# piglow.net
KiCad netlist of a schematic drawn in EAGLE
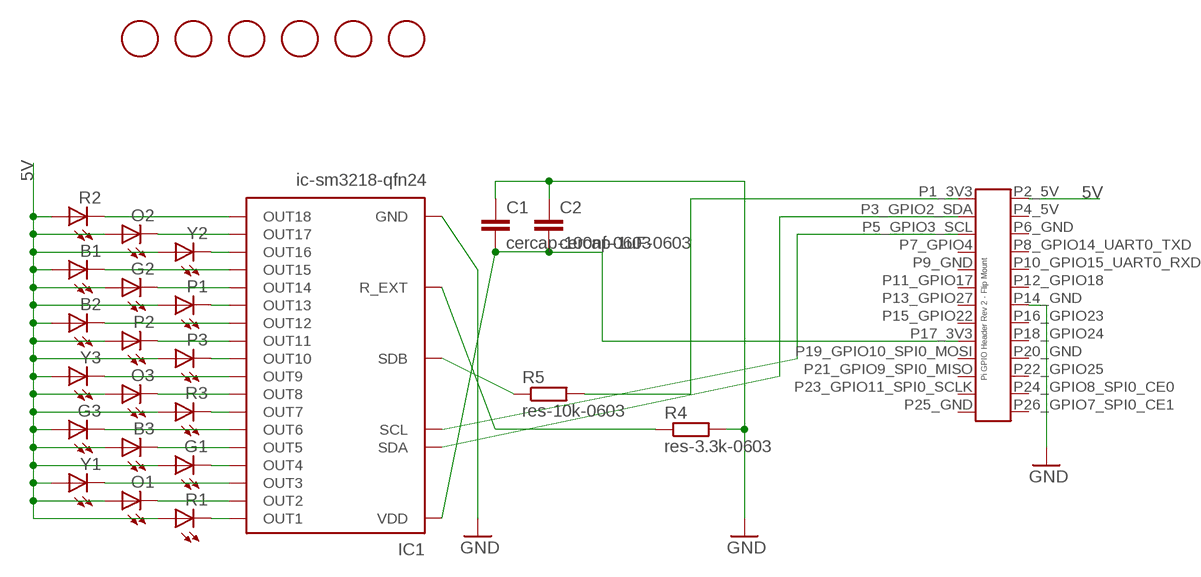
[diagram p0: schematic, sheet 1]

(export (version "E")
  (design (tool "Eeschema 10.0.6"))
  (components
    (comp (ref "B1")
      (value "led-blue-0805")
      (footprint "eagle-import:CHIPLED_0805")
      (libsource (lib "eagle-import") (part "LEDCHIPLED_0805"))
    )
    (comp (ref "B2")
      (value "led-blue-0805")
      (footprint "eagle-import:CHIPLED_0805")
      (libsource (lib "eagle-import") (part "LEDCHIPLED_0805"))
    )
    (comp (ref "B3")
      (value "led-blue-0805")
      (footprint "eagle-import:CHIPLED_0805")
      (libsource (lib "eagle-import") (part "LEDCHIPLED_0805"))
    )
    (comp (ref "C1")
      (value "cercap-100nf-0603")
      (footprint "eagle-import:C0603K")
      (libsource (lib "eagle-import") (part "C-EUC0603K"))
    )
    (comp (ref "C2")
      (value "cercap-1uF-0603")
      (footprint "eagle-import:C0603K")
      (libsource (lib "eagle-import") (part "C-EUC0603K"))
    )
    (comp (ref "G1")
      (value "led-green-0805")
      (footprint "eagle-import:CHIPLED_0805")
      (libsource (lib "eagle-import") (part "LEDCHIPLED_0805"))
    )
    (comp (ref "G2")
      (value "led-green-0805")
      (footprint "eagle-import:CHIPLED_0805")
      (libsource (lib "eagle-import") (part "LEDCHIPLED_0805"))
    )
    (comp (ref "G3")
      (value "led-green-0805")
      (footprint "eagle-import:CHIPLED_0805")
      (libsource (lib "eagle-import") (part "LEDCHIPLED_0805"))
    )
    (comp (ref "IC1")
      (value "ic-sm3218-qfn24")
      (footprint "eagle-import:QFN24")
      (libsource (lib "eagle-import") (part "SN3218"))
    )
    (comp (ref "O1")
      (value "led-orange-0805")
      (footprint "eagle-import:CHIPLED_0805")
      (libsource (lib "eagle-import") (part "LEDCHIPLED_0805"))
    )
    (comp (ref "O2")
      (value "led-orange-0805")
      (footprint "eagle-import:CHIPLED_0805")
      (libsource (lib "eagle-import") (part "LEDCHIPLED_0805"))
    )
    (comp (ref "O3")
      (value "led-orange-0805")
      (footprint "eagle-import:CHIPLED_0805")
      (libsource (lib "eagle-import") (part "LEDCHIPLED_0805"))
    )
    (comp (ref "P1")
      (value "led-pink-0805")
      (footprint "eagle-import:CHIPLED_0805")
      (libsource (lib "eagle-import") (part "LEDCHIPLED_0805"))
    )
    (comp (ref "P2")
      (value "led-pink-0805")
      (footprint "eagle-import:CHIPLED_0805")
      (libsource (lib "eagle-import") (part "LEDCHIPLED_0805"))
    )
    (comp (ref "P3")
      (value "led-pink-0805")
      (footprint "eagle-import:CHIPLED_0805")
      (libsource (lib "eagle-import") (part "LEDCHIPLED_0805"))
    )
    (comp (ref "R1")
      (value "led-red-0805")
      (footprint "eagle-import:CHIPLED_0805")
      (libsource (lib "eagle-import") (part "LEDCHIPLED_0805"))
    )
    (comp (ref "R2")
      (value "led-red-0805")
      (footprint "eagle-import:CHIPLED_0805")
      (libsource (lib "eagle-import") (part "LEDCHIPLED_0805"))
    )
    (comp (ref "R3")
      (value "led-red-0805")
      (footprint "eagle-import:CHIPLED_0805")
      (libsource (lib "eagle-import") (part "LEDCHIPLED_0805"))
    )
    (comp (ref "R4")
      (value "res-3.3k-0603")
      (footprint "eagle-import:R0603")
      (libsource (lib "eagle-import") (part "R-EU_R0603"))
    )
    (comp (ref "R5")
      (value "res-10k-0603")
      (footprint "eagle-import:R0603@1")
      (libsource (lib "eagle-import") (part "resistor_R-EU_R0603"))
    )
    (comp (ref "U$1")
      (value "FIDUCIAL")
      (footprint "eagle-import:FIDUCIAL_1MM")
      (libsource (lib "eagle-import") (part "FIDUCIAL"))
    )
    (comp (ref "U$2")
      (value "FIDUCIAL")
      (footprint "eagle-import:FIDUCIAL_1MM")
      (libsource (lib "eagle-import") (part "FIDUCIAL"))
    )
    (comp (ref "U$3")
      (value "FIDUCIAL")
      (footprint "eagle-import:FIDUCIAL_1MM")
      (libsource (lib "eagle-import") (part "FIDUCIAL"))
    )
    (comp (ref "U$4")
      (value "FCI_89898_313LF_26P_CONNECTOR_SMT_FLIPPED")
      (footprint "eagle-import:FCI_89898_313LF_26P_CONNECTOR_SMT_FLIPPED")
      (libsource (lib "eagle-import") (part "FCI_89898_313LF_26P_CONNECTOR_SMT_FLIPPED"))
    )
    (comp (ref "U$5")
      (value "FIDUCIAL")
      (footprint "eagle-import:FIDUCIAL_1MM")
      (libsource (lib "eagle-import") (part "FIDUCIAL"))
    )
    (comp (ref "U$6")
      (value "FIDUCIAL")
      (footprint "eagle-import:FIDUCIAL_1MM")
      (libsource (lib "eagle-import") (part "FIDUCIAL"))
    )
    (comp (ref "U$7")
      (value "FIDUCIAL")
      (footprint "eagle-import:FIDUCIAL_1MM")
      (libsource (lib "eagle-import") (part "FIDUCIAL"))
    )
    (comp (ref "Y1")
      (value "led-yellow-0805")
      (footprint "eagle-import:CHIPLED_0805")
      (libsource (lib "eagle-import") (part "LEDCHIPLED_0805"))
    )
    (comp (ref "Y2")
      (value "led-yellow-0805")
      (footprint "eagle-import:CHIPLED_0805")
      (libsource (lib "eagle-import") (part "LEDCHIPLED_0805"))
    )
    (comp (ref "Y3")
      (value "led-yellow-0805")
      (footprint "eagle-import:CHIPLED_0805")
      (libsource (lib "eagle-import") (part "LEDCHIPLED_0805"))
    )
  )
  (nets
    (net (code "1") (name "/5V") (class "Default")
      (node (ref "B1") (pin "A") (pinfunction "A_A") (pintype "passive"))
      (node (ref "B2") (pin "A") (pinfunction "A_A") (pintype "passive"))
      (node (ref "B3") (pin "A") (pinfunction "A_A") (pintype "passive"))
      (node (ref "G1") (pin "A") (pinfunction "A_A") (pintype "passive"))
      (node (ref "G2") (pin "A") (pinfunction "A_A") (pintype "passive"))
      (node (ref "G3") (pin "A") (pinfunction "A_A") (pintype "passive"))
      (node (ref "O1") (pin "A") (pinfunction "A_A") (pintype "passive"))
      (node (ref "O2") (pin "A") (pinfunction "A_A") (pintype "passive"))
      (node (ref "O3") (pin "A") (pinfunction "A_A") (pintype "passive"))
      (node (ref "P1") (pin "A") (pinfunction "A_A") (pintype "passive"))
      (node (ref "P2") (pin "A") (pinfunction "A_A") (pintype "passive"))
      (node (ref "P3") (pin "A") (pinfunction "A_A") (pintype "passive"))
      (node (ref "R1") (pin "A") (pinfunction "A_A") (pintype "passive"))
      (node (ref "R2") (pin "A") (pinfunction "A_A") (pintype "passive"))
      (node (ref "R3") (pin "A") (pinfunction "A_A") (pintype "passive"))
      (node (ref "U$4") (pin "P2_5V") (pinfunction "P2_5V_P2_5V") (pintype "power_in"))
      (node (ref "Y1") (pin "A") (pinfunction "A_A") (pintype "passive"))
      (node (ref "Y2") (pin "A") (pinfunction "A_A") (pintype "passive"))
      (node (ref "Y3") (pin "A") (pinfunction "A_A") (pintype "passive"))
    )
    (net (code "2") (name "/P4_5V") (class "Default")
      (node (ref "U$4") (pin "P4_5V") (pinfunction "P4_5V_P4_5V") (pintype "power_in"))
    )
    (net (code "3") (name "GND") (class "Default")
      (node (ref "C1") (pin "1") (pinfunction "1_1") (pintype "passive"))
      (node (ref "C2") (pin "1") (pinfunction "1_1") (pintype "passive"))
      (node (ref "IC1") (pin "4") (pinfunction "GND_4") (pintype "bidirectional"))
      (node (ref "IC1") (pin "GND") (pinfunction "GND_GND") (pintype "bidirectional"))
      (node (ref "R4") (pin "2") (pinfunction "2_2") (pintype "passive"))
      (node (ref "U$4") (pin "P14_GND") (pinfunction "P14_GND_P14_GND") (pintype "passive"))
    )
    (net (code "4") (name "Net-(IC1-OUT1)") (class "Default")
      (node (ref "IC1") (pin "7") (pinfunction "OUT1_7") (pintype "bidirectional"))
      (node (ref "R1") (pin "C") (pinfunction "C_C") (pintype "passive"))
    )
    (net (code "5") (name "Net-(IC1-OUT2)") (class "Default")
      (node (ref "IC1") (pin "8") (pinfunction "OUT2_8") (pintype "bidirectional"))
      (node (ref "O1") (pin "C") (pinfunction "C_C") (pintype "passive"))
    )
    (net (code "6") (name "Net-(IC1-OUT3)") (class "Default")
      (node (ref "IC1") (pin "9") (pinfunction "OUT3_9") (pintype "bidirectional"))
      (node (ref "Y1") (pin "C") (pinfunction "C_C") (pintype "passive"))
    )
    (net (code "7") (name "Net-(IC1-OUT4)") (class "Default")
      (node (ref "G1") (pin "C") (pinfunction "C_C") (pintype "passive"))
      (node (ref "IC1") (pin "10") (pinfunction "OUT4_10") (pintype "bidirectional"))
    )
    (net (code "8") (name "Net-(IC1-OUT5)") (class "Default")
      (node (ref "B3") (pin "C") (pinfunction "C_C") (pintype "passive"))
      (node (ref "IC1") (pin "11") (pinfunction "OUT5_11") (pintype "bidirectional"))
    )
    (net (code "9") (name "Net-(IC1-OUT6)") (class "Default")
      (node (ref "G3") (pin "C") (pinfunction "C_C") (pintype "passive"))
      (node (ref "IC1") (pin "12") (pinfunction "OUT6_12") (pintype "bidirectional"))
    )
    (net (code "10") (name "Net-(IC1-OUT7)") (class "Default")
      (node (ref "IC1") (pin "13") (pinfunction "OUT7_13") (pintype "bidirectional"))
      (node (ref "R3") (pin "C") (pinfunction "C_C") (pintype "passive"))
    )
    (net (code "11") (name "Net-(IC1-OUT8)") (class "Default")
      (node (ref "IC1") (pin "14") (pinfunction "OUT8_14") (pintype "bidirectional"))
      (node (ref "O3") (pin "C") (pinfunction "C_C") (pintype "passive"))
    )
    (net (code "12") (name "Net-(IC1-OUT9)") (class "Default")
      (node (ref "IC1") (pin "15") (pinfunction "OUT9_15") (pintype "bidirectional"))
      (node (ref "Y3") (pin "C") (pinfunction "C_C") (pintype "passive"))
    )
    (net (code "13") (name "Net-(IC1-OUT10)") (class "Default")
      (node (ref "IC1") (pin "16") (pinfunction "OUT10_16") (pintype "bidirectional"))
      (node (ref "P3") (pin "C") (pinfunction "C_C") (pintype "passive"))
    )
    (net (code "14") (name "Net-(IC1-OUT11)") (class "Default")
      (node (ref "IC1") (pin "17") (pinfunction "OUT11_17") (pintype "bidirectional"))
      (node (ref "P2") (pin "C") (pinfunction "C_C") (pintype "passive"))
    )
    (net (code "15") (name "Net-(IC1-OUT12)") (class "Default")
      (node (ref "B2") (pin "C") (pinfunction "C_C") (pintype "passive"))
      (node (ref "IC1") (pin "18") (pinfunction "OUT12_18") (pintype "bidirectional"))
    )
    (net (code "16") (name "Net-(IC1-OUT13)") (class "Default")
      (node (ref "IC1") (pin "19") (pinfunction "OUT13_19") (pintype "bidirectional"))
      (node (ref "P1") (pin "C") (pinfunction "C_C") (pintype "passive"))
    )
    (net (code "17") (name "Net-(IC1-OUT14)") (class "Default")
      (node (ref "G2") (pin "C") (pinfunction "C_C") (pintype "passive"))
      (node (ref "IC1") (pin "20") (pinfunction "OUT14_20") (pintype "bidirectional"))
    )
    (net (code "18") (name "Net-(IC1-OUT15)") (class "Default")
      (node (ref "B1") (pin "C") (pinfunction "C_C") (pintype "passive"))
      (node (ref "IC1") (pin "21") (pinfunction "OUT15_21") (pintype "bidirectional"))
    )
    (net (code "19") (name "Net-(IC1-OUT16)") (class "Default")
      (node (ref "IC1") (pin "22") (pinfunction "OUT16_22") (pintype "bidirectional"))
      (node (ref "Y2") (pin "C") (pinfunction "C_C") (pintype "passive"))
    )
    (net (code "20") (name "Net-(IC1-OUT17)") (class "Default")
      (node (ref "IC1") (pin "23") (pinfunction "OUT17_23") (pintype "bidirectional"))
      (node (ref "O2") (pin "C") (pinfunction "C_C") (pintype "passive"))
    )
    (net (code "21") (name "Net-(IC1-OUT18)") (class "Default")
      (node (ref "IC1") (pin "1") (pinfunction "OUT18_1") (pintype "bidirectional"))
      (node (ref "R2") (pin "C") (pinfunction "C_C") (pintype "passive"))
    )
    (net (code "22") (name "Net-(IC1-R_EXT)") (class "Default")
      (node (ref "IC1") (pin "2") (pinfunction "R_EXT_2") (pintype "bidirectional"))
      (node (ref "R4") (pin "1") (pinfunction "1_1") (pintype "passive"))
    )
    (net (code "23") (name "Net-(IC1-SCL)") (class "Default")
      (node (ref "IC1") (pin "6") (pinfunction "SCL_6") (pintype "bidirectional"))
      (node (ref "U$4") (pin "P5_GPIO3_SCL") (pinfunction "P5_GPIO3_SCL_P5_GPIO3_SCL") (pintype "bidirectional"))
    )
    (net (code "24") (name "Net-(IC1-SDA)") (class "Default")
      (node (ref "IC1") (pin "5") (pinfunction "SDA_5") (pintype "bidirectional"))
      (node (ref "U$4") (pin "P3_GPIO2_SDA") (pinfunction "P3_GPIO2_SDA_P3_GPIO2_SDA") (pintype "bidirectional"))
    )
    (net (code "25") (name "Net-(IC1-SDB)") (class "Default")
      (node (ref "IC1") (pin "24") (pinfunction "SDB_24") (pintype "bidirectional"))
      (node (ref "R5") (pin "1") (pinfunction "1_1") (pintype "passive"))
    )
    (net (code "26") (name "Net-(IC1-VDD)") (class "Default")
      (node (ref "C1") (pin "2") (pinfunction "2_2") (pintype "passive"))
      (node (ref "C2") (pin "2") (pinfunction "2_2") (pintype "passive"))
      (node (ref "IC1") (pin "3") (pinfunction "VDD_3") (pintype "bidirectional"))
      (node (ref "U$4") (pin "P17_3V3") (pinfunction "P17_3V3_P17_3V3") (pintype "power_in"))
    )
    (net (code "27") (name "Net-(R5-Pad2)") (class "Default")
      (node (ref "R5") (pin "2") (pinfunction "2_2") (pintype "passive"))
      (node (ref "U$4") (pin "P1_3V3") (pinfunction "P1_3V3_P1_3V3") (pintype "power_in"))
    )
    (net (code "28") (name "unconnected-(U$4-PadP6_GND)") (class "Default")
      (node (ref "U$4") (pin "P6_GND") (pinfunction "P6_GND_P6_GND") (pintype "passive"))
    )
    (net (code "29") (name "unconnected-(U$4-PadP7_GPIO4)") (class "Default")
      (node (ref "U$4") (pin "P7_GPIO4") (pinfunction "P7_GPIO4_P7_GPIO4") (pintype "bidirectional"))
    )
    (net (code "30") (name "unconnected-(U$4-PadP8_GPIO14_UART0_TXD)") (class "Default")
      (node (ref "U$4") (pin "P8_GPIO14_UART0_TXD") (pinfunction "P8_GPIO14_UART0_TXD_P8_GPIO14_UART0_TXD") (pintype "bidirectional"))
    )
    (net (code "31") (name "unconnected-(U$4-PadP9_GND)") (class "Default")
      (node (ref "U$4") (pin "P9_GND") (pinfunction "P9_GND_P9_GND") (pintype "passive"))
    )
    (net (code "32") (name "unconnected-(U$4-PadP10_GPIO15_UART0_RXD)") (class "Default")
      (node (ref "U$4") (pin "P10_GPIO15_UART0_RXD") (pinfunction "P10_GPIO15_UART0_RXD_P10_GPIO15_UART0_RXD") (pintype "bidirectional"))
    )
    (net (code "33") (name "unconnected-(U$4-PadP11_GPIO17)") (class "Default")
      (node (ref "U$4") (pin "P11_GPIO17") (pinfunction "P11_GPIO17_P11_GPIO17") (pintype "bidirectional"))
    )
    (net (code "34") (name "unconnected-(U$4-PadP12_GPIO18)") (class "Default")
      (node (ref "U$4") (pin "P12_GPIO18") (pinfunction "P12_GPIO18_P12_GPIO18") (pintype "bidirectional"))
    )
    (net (code "35") (name "unconnected-(U$4-PadP13_GPIO27)") (class "Default")
      (node (ref "U$4") (pin "P13_GPIO27") (pinfunction "P13_GPIO27_P13_GPIO27") (pintype "bidirectional"))
    )
    (net (code "36") (name "unconnected-(U$4-PadP15_GPIO22)") (class "Default")
      (node (ref "U$4") (pin "P15_GPIO22") (pinfunction "P15_GPIO22_P15_GPIO22") (pintype "bidirectional"))
    )
    (net (code "37") (name "unconnected-(U$4-PadP16_GPIO23)") (class "Default")
      (node (ref "U$4") (pin "P16_GPIO23") (pinfunction "P16_GPIO23_P16_GPIO23") (pintype "bidirectional"))
    )
    (net (code "38") (name "unconnected-(U$4-PadP18_GPIO24)") (class "Default")
      (node (ref "U$4") (pin "P18_GPIO24") (pinfunction "P18_GPIO24_P18_GPIO24") (pintype "bidirectional"))
    )
    (net (code "39") (name "unconnected-(U$4-PadP19_GPIO10_SPI0_MOSI)") (class "Default")
      (node (ref "U$4") (pin "P19_GPIO10_SPI0_MOSI") (pinfunction "P19_GPIO10_SPI0_MOSI_P19_GPIO10_SPI0_MOSI") (pintype "bidirectional"))
    )
    (net (code "40") (name "unconnected-(U$4-PadP20_GND)") (class "Default")
      (node (ref "U$4") (pin "P20_GND") (pinfunction "P20_GND_P20_GND") (pintype "passive"))
    )
    (net (code "41") (name "unconnected-(U$4-PadP21_GPIO9_SPI0_MISO)") (class "Default")
      (node (ref "U$4") (pin "P21_GPIO9_SPI0_MISO") (pinfunction "P21_GPIO9_SPI0_MISO_P21_GPIO9_SPI0_MISO") (pintype "bidirectional"))
    )
    (net (code "42") (name "unconnected-(U$4-PadP22_GPIO25)") (class "Default")
      (node (ref "U$4") (pin "P22_GPIO25") (pinfunction "P22_GPIO25_P22_GPIO25") (pintype "bidirectional"))
    )
    (net (code "43") (name "unconnected-(U$4-PadP23_GPIO11_SPI0_SCLK)") (class "Default")
      (node (ref "U$4") (pin "P23_GPIO11_SPI0_SCLK") (pinfunction "P23_GPIO11_SPI0_SCLK_P23_GPIO11_SPI0_SCLK") (pintype "bidirectional"))
    )
    (net (code "44") (name "unconnected-(U$4-PadP24_GPIO8_SPI0_CE0)") (class "Default")
      (node (ref "U$4") (pin "P24_GPIO8_SPI0_CE0") (pinfunction "P24_GPIO8_SPI0_CE0_P24_GPIO8_SPI0_CE0") (pintype "bidirectional"))
    )
    (net (code "45") (name "unconnected-(U$4-PadP25_GND)") (class "Default")
      (node (ref "U$4") (pin "P25_GND") (pinfunction "P25_GND_P25_GND") (pintype "passive"))
    )
    (net (code "46") (name "unconnected-(U$4-PadP26_GPIO7_SPI0_CE1)") (class "Default")
      (node (ref "U$4") (pin "P26_GPIO7_SPI0_CE1") (pinfunction "P26_GPIO7_SPI0_CE1_P26_GPIO7_SPI0_CE1") (pintype "bidirectional"))
    )
  )
)
